# SCH_HackerCard_2024-03-12.net
KiCad netlist of a schematic drawn in EasyEDA
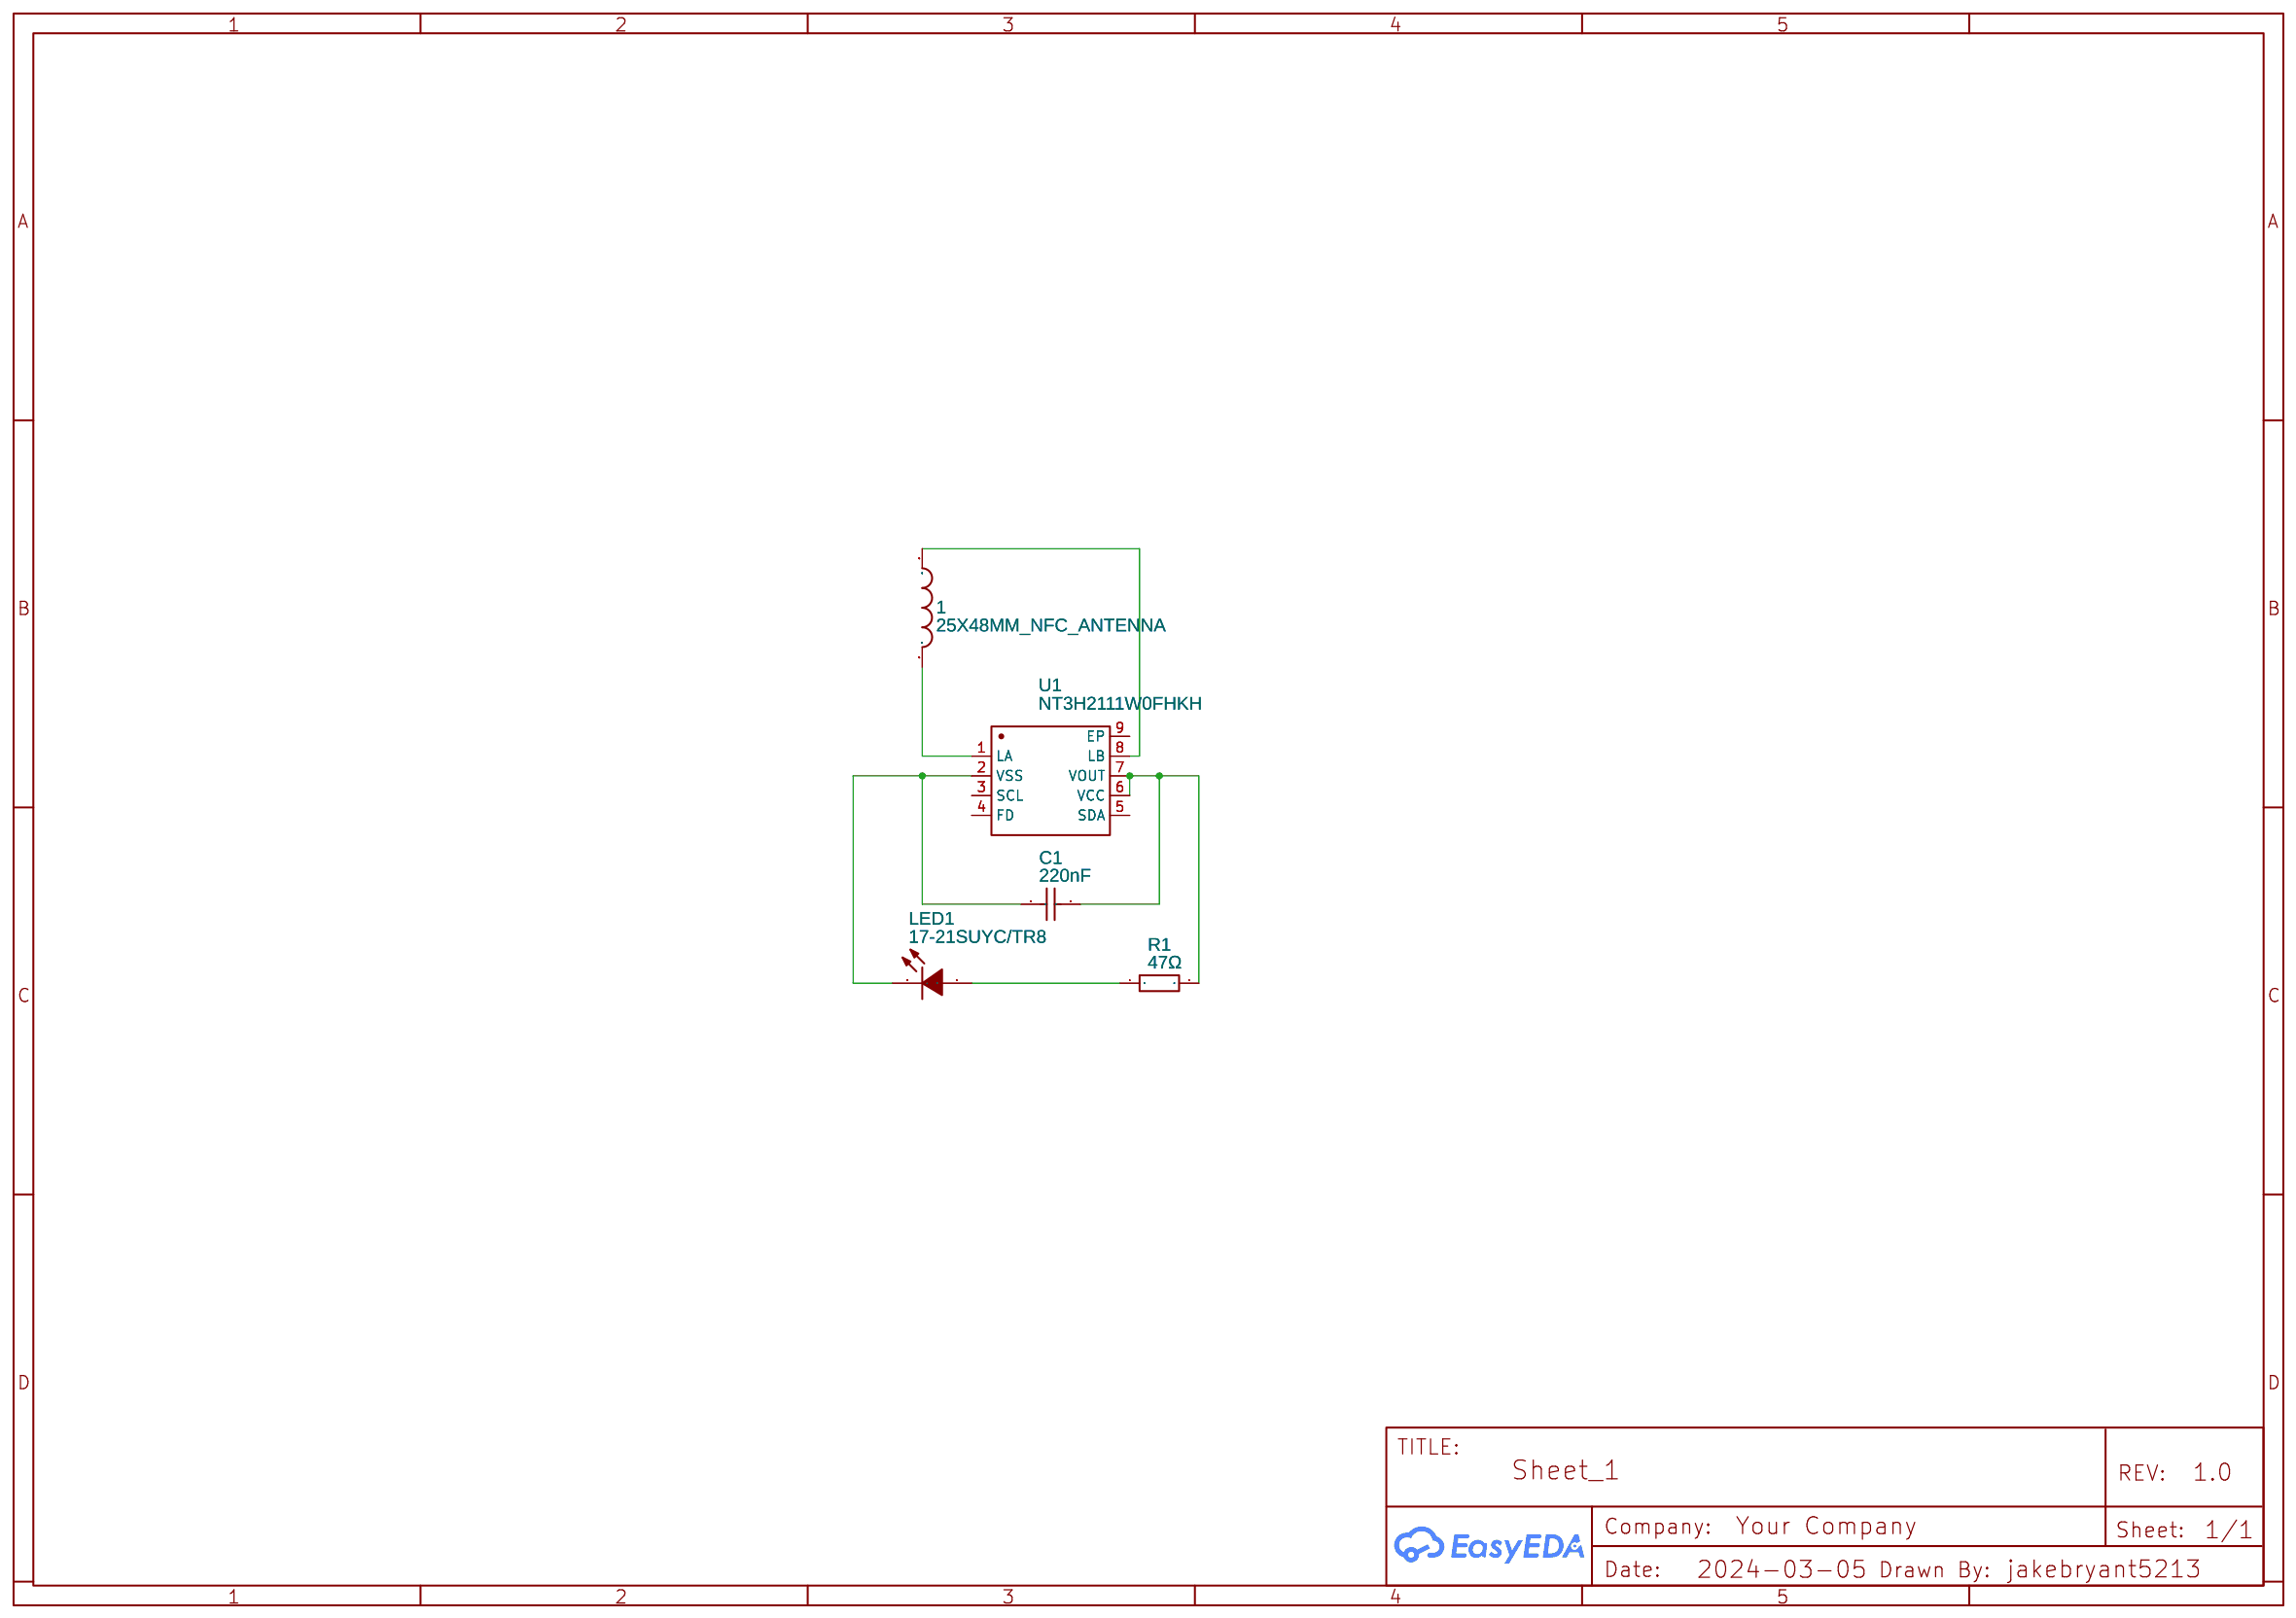
[diagram p0: schematic sheet]

(export (version "E")
  (design (tool "Eeschema 10.0.6"))
  (components
    (comp (ref "1") (value "25X48MM_NFC_ANTENNA") (libsource (lib "") (part "25X48MM_NFC_ANTENNA")))
    (comp (ref "C1")
      (value "220nF")
      (fields
        (field (name "Manufacturer Part") "CL10B224KA8NNNC")
        (field (name "Manufacturer") "SAMSUNG(三星)")
      )
      (libsource (lib "") (part "CL10B224KA8NNNC"))
    )
    (comp (ref "LED1")
      (value "17-21SUYC/TR8")
      (fields (field (name "Manufacturer Part") "KT-0805黄灯") (field (name "Manufacturer") "KENTO"))
      (libsource (lib "") (part "17-21SUYC/TR8"))
    )
    (comp (ref "R1")
      (value "47Ω")
      (fields
        (field (name "Manufacturer Part") "0603WAF470JT5E")
        (field (name "Manufacturer") "UNI-ROYAL(厚声)")
      )
      (libsource (lib "") (part "0603WAF470JT5E"))
    )
    (comp (ref "U1")
      (value "NT3H2111W0FHKH")
      (fields (field (name "Manufacturer") "NXP(恩智浦)"))
      (libsource (lib "") (part "NT3H2111W0FHKH"))
    )
  )
  (nets
    (net (code "1") (name "Net-(LED1-+)") (class "Default")
      (node (ref "LED1") (pin "1") (pinfunction "+_1") (pintype "unspecified"))
      (node (ref "R1") (pin "1") (pinfunction "1_1") (pintype "input"))
    )
    (net (code "2") (name "Net-(LED1--)") (class "Default")
      (node (ref "C1") (pin "1") (pinfunction "1_1") (pintype "input"))
      (node (ref "LED1") (pin "2") (pinfunction "-_2") (pintype "unspecified"))
      (node (ref "U1") (pin "2") (pinfunction "VSS_2") (pintype "unspecified"))
    )
    (net (code "3") (name "Net-(U1-LA)") (class "Default")
      (node (ref "1") (pin "P$2") (pinfunction "P$2_P$2") (pintype "bidirectional"))
      (node (ref "U1") (pin "1") (pinfunction "LA_1") (pintype "unspecified"))
    )
    (net (code "4") (name "Net-(U1-LB)") (class "Default")
      (node (ref "1") (pin "P$1") (pinfunction "P$1_P$1") (pintype "bidirectional"))
      (node (ref "U1") (pin "8") (pinfunction "LB_8") (pintype "unspecified"))
    )
    (net (code "5") (name "Net-(U1-VCC)") (class "Default")
      (node (ref "C1") (pin "2") (pinfunction "2_2") (pintype "input"))
      (node (ref "R1") (pin "2") (pinfunction "2_2") (pintype "input"))
      (node (ref "U1") (pin "6") (pinfunction "VCC_6") (pintype "unspecified"))
      (node (ref "U1") (pin "7") (pinfunction "VOUT_7") (pintype "unspecified"))
    )
    (net (code "6") (name "unconnected-(U1-EP-Pad9)") (class "Default")
      (node (ref "U1") (pin "9") (pinfunction "EP_9") (pintype "unspecified"))
    )
    (net (code "7") (name "unconnected-(U1-FD-Pad4)") (class "Default")
      (node (ref "U1") (pin "4") (pinfunction "FD_4") (pintype "unspecified"))
    )
    (net (code "8") (name "unconnected-(U1-SCL-Pad3)") (class "Default")
      (node (ref "U1") (pin "3") (pinfunction "SCL_3") (pintype "unspecified"))
    )
    (net (code "9") (name "unconnected-(U1-SDA-Pad5)") (class "Default")
      (node (ref "U1") (pin "5") (pinfunction "SDA_5") (pintype "unspecified"))
    )
  )
)
